# MacroPad.net
KiCad netlist of a schematic drawn in EAGLE
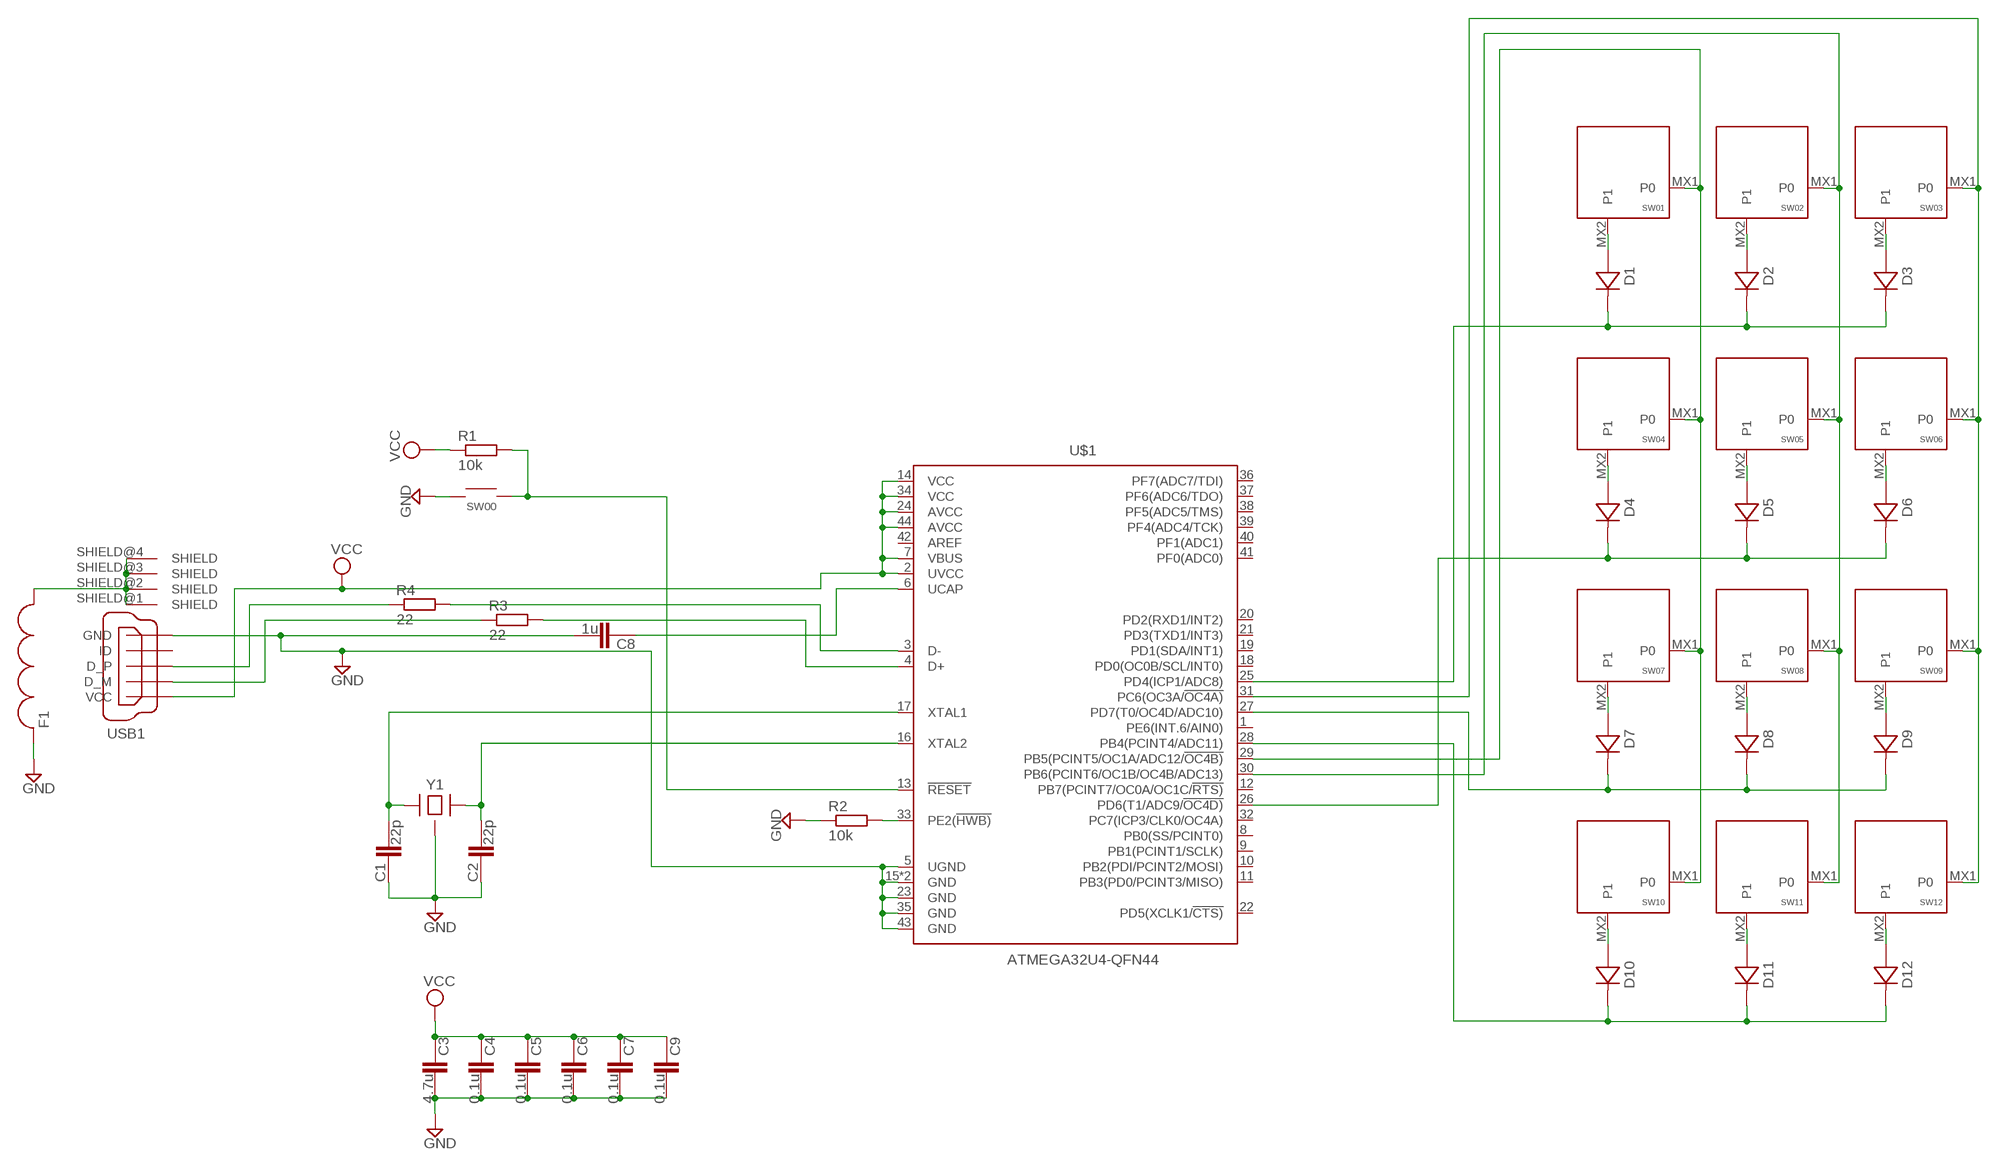
[diagram p0: schematic, sheet 1]

(export (version "E")
  (design (tool "Eeschema 10.0.6"))
  (components
    (comp (ref "C1")
      (value "22p")
      (footprint "eagle-import:C0603")
      (libsource (lib "eagle-import") (part "CAPACITOR-0603"))
    )
    (comp (ref "C2")
      (value "22p")
      (footprint "eagle-import:C0603")
      (libsource (lib "eagle-import") (part "CAPACITOR-0603"))
    )
    (comp (ref "C3")
      (value "4.7u")
      (footprint "eagle-import:C0603")
      (libsource (lib "eagle-import") (part "CAPACITOR-0603"))
    )
    (comp (ref "C4")
      (value "0.1u")
      (footprint "eagle-import:C0603")
      (libsource (lib "eagle-import") (part "CAPACITOR-0603"))
    )
    (comp (ref "C5")
      (value "0.1u")
      (footprint "eagle-import:C0603")
      (libsource (lib "eagle-import") (part "CAPACITOR-0603"))
    )
    (comp (ref "C6")
      (value "0.1u")
      (footprint "eagle-import:C0603")
      (libsource (lib "eagle-import") (part "CAPACITOR-0603"))
    )
    (comp (ref "C7")
      (value "0.1u")
      (footprint "eagle-import:C0603")
      (libsource (lib "eagle-import") (part "CAPACITOR-0603"))
    )
    (comp (ref "C8")
      (value "1u")
      (footprint "eagle-import:C0603")
      (libsource (lib "eagle-import") (part "CAPACITOR-0603"))
    )
    (comp (ref "C9")
      (value "0.1u")
      (footprint "eagle-import:C0603")
      (libsource (lib "eagle-import") (part "CAPACITOR-0603"))
    )
    (comp (ref "D1")
      (value "DIODE-DFN0603-2")
      (footprint "eagle-import:DFN0603-2")
      (libsource (lib "eagle-import") (part "DIODE-DFN0603-2"))
    )
    (comp (ref "D2")
      (value "DIODE-DFN0603-2")
      (footprint "eagle-import:DFN0603-2")
      (libsource (lib "eagle-import") (part "DIODE-DFN0603-2"))
    )
    (comp (ref "D3")
      (value "DIODE-DFN0603-2")
      (footprint "eagle-import:DFN0603-2")
      (libsource (lib "eagle-import") (part "DIODE-DFN0603-2"))
    )
    (comp (ref "D4")
      (value "DIODE-DFN0603-2")
      (footprint "eagle-import:DFN0603-2")
      (libsource (lib "eagle-import") (part "DIODE-DFN0603-2"))
    )
    (comp (ref "D5")
      (value "DIODE-DFN0603-2")
      (footprint "eagle-import:DFN0603-2")
      (libsource (lib "eagle-import") (part "DIODE-DFN0603-2"))
    )
    (comp (ref "D6")
      (value "DIODE-DFN0603-2")
      (footprint "eagle-import:DFN0603-2")
      (libsource (lib "eagle-import") (part "DIODE-DFN0603-2"))
    )
    (comp (ref "D7")
      (value "DIODE-DFN0603-2")
      (footprint "eagle-import:DFN0603-2")
      (libsource (lib "eagle-import") (part "DIODE-DFN0603-2"))
    )
    (comp (ref "D8")
      (value "DIODE-DFN0603-2")
      (footprint "eagle-import:DFN0603-2")
      (libsource (lib "eagle-import") (part "DIODE-DFN0603-2"))
    )
    (comp (ref "D9")
      (value "DIODE-DFN0603-2")
      (footprint "eagle-import:DFN0603-2")
      (libsource (lib "eagle-import") (part "DIODE-DFN0603-2"))
    )
    (comp (ref "D10")
      (value "DIODE-DFN0603-2")
      (footprint "eagle-import:DFN0603-2")
      (libsource (lib "eagle-import") (part "DIODE-DFN0603-2"))
    )
    (comp (ref "D11")
      (value "DIODE-DFN0603-2")
      (footprint "eagle-import:DFN0603-2")
      (libsource (lib "eagle-import") (part "DIODE-DFN0603-2"))
    )
    (comp (ref "D12")
      (value "DIODE-DFN0603-2")
      (footprint "eagle-import:DFN0603-2")
      (libsource (lib "eagle-import") (part "DIODE-DFN0603-2"))
    )
    (comp (ref "F1")
      (value "FERRITE-0805")
      (footprint "eagle-import:F0805")
      (libsource (lib "eagle-import") (part "FERRITE-0805"))
    )
    (comp (ref "R1")
      (value "10k")
      (footprint "eagle-import:R0603")
      (libsource (lib "eagle-import") (part "RESISTOR-0603"))
    )
    (comp (ref "R2")
      (value "10k")
      (footprint "eagle-import:R0603")
      (libsource (lib "eagle-import") (part "RESISTOR-0603"))
    )
    (comp (ref "R3")
      (value "22")
      (footprint "eagle-import:R0603")
      (libsource (lib "eagle-import") (part "RESISTOR-0603"))
    )
    (comp (ref "R4")
      (value "22")
      (footprint "eagle-import:R0603")
      (libsource (lib "eagle-import") (part "RESISTOR-0603"))
    )
    (comp (ref "SW00")
      (value "SWITCH-SMD-EVQP-P2602W")
      (footprint "eagle-import:SWITCH-SMD-EVQP-P2602W")
      (libsource (lib "eagle-import") (part "SWITCH-SMD-EVQP-P2602W"))
    )
    (comp (ref "SW01")
      (value "KEYSWITCH-PLAIN-MX-1U")
      (footprint "eagle-import:MX-1U")
      (libsource (lib "eagle-import") (part "KEYSWITCH-PLAIN-MX-1U"))
    )
    (comp (ref "SW02")
      (value "KEYSWITCH-PLAIN-MX-1U")
      (footprint "eagle-import:MX-1U")
      (libsource (lib "eagle-import") (part "KEYSWITCH-PLAIN-MX-1U"))
    )
    (comp (ref "SW03")
      (value "KEYSWITCH-PLAIN-MX-1U")
      (footprint "eagle-import:MX-1U")
      (libsource (lib "eagle-import") (part "KEYSWITCH-PLAIN-MX-1U"))
    )
    (comp (ref "SW04")
      (value "KEYSWITCH-PLAIN-MX-1U")
      (footprint "eagle-import:MX-1U")
      (libsource (lib "eagle-import") (part "KEYSWITCH-PLAIN-MX-1U"))
    )
    (comp (ref "SW05")
      (value "KEYSWITCH-PLAIN-MX-1U")
      (footprint "eagle-import:MX-1U")
      (libsource (lib "eagle-import") (part "KEYSWITCH-PLAIN-MX-1U"))
    )
    (comp (ref "SW06")
      (value "KEYSWITCH-PLAIN-MX-1U")
      (footprint "eagle-import:MX-1U")
      (libsource (lib "eagle-import") (part "KEYSWITCH-PLAIN-MX-1U"))
    )
    (comp (ref "SW07")
      (value "KEYSWITCH-PLAIN-MX-1U")
      (footprint "eagle-import:MX-1U")
      (libsource (lib "eagle-import") (part "KEYSWITCH-PLAIN-MX-1U"))
    )
    (comp (ref "SW08")
      (value "KEYSWITCH-PLAIN-MX-1U")
      (footprint "eagle-import:MX-1U")
      (libsource (lib "eagle-import") (part "KEYSWITCH-PLAIN-MX-1U"))
    )
    (comp (ref "SW09")
      (value "KEYSWITCH-PLAIN-MX-1U")
      (footprint "eagle-import:MX-1U")
      (libsource (lib "eagle-import") (part "KEYSWITCH-PLAIN-MX-1U"))
    )
    (comp (ref "SW10")
      (value "KEYSWITCH-PLAIN-MX-1U")
      (footprint "eagle-import:MX-1U")
      (libsource (lib "eagle-import") (part "KEYSWITCH-PLAIN-MX-1U"))
    )
    (comp (ref "SW11")
      (value "KEYSWITCH-PLAIN-MX-1U")
      (footprint "eagle-import:MX-1U")
      (libsource (lib "eagle-import") (part "KEYSWITCH-PLAIN-MX-1U"))
    )
    (comp (ref "SW12")
      (value "KEYSWITCH-PLAIN-MX-1U")
      (footprint "eagle-import:MX-1U")
      (libsource (lib "eagle-import") (part "KEYSWITCH-PLAIN-MX-1U"))
    )
    (comp (ref "U$1")
      (value "ATMEGA32U4-QFN44")
      (footprint "eagle-import:QFN-44")
      (libsource (lib "eagle-import") (part "ATMEGA32U4-QFN44"))
    )
    (comp (ref "USB1")
      (value "USB_CONN-MINI-FEMALE")
      (footprint "eagle-import:UX60-MB-5S8")
      (libsource (lib "eagle-import") (part "USB_CONN-MINI-FEMALE"))
    )
    (comp (ref "Y1")
      (value "CRYSTAL-4PIN-3.2X2.5")
      (footprint "eagle-import:CRYSTAL-3.2X2.5")
      (libsource (lib "eagle-import") (part "CRYSTAL-4PIN-3.2X2.5"))
    )
  )
  (nets
    (net (code "1") (name "GND") (class "Default")
      (node (ref "C1") (pin "1") (pinfunction "1_1") (pintype "passive"))
      (node (ref "C2") (pin "1") (pinfunction "1_1") (pintype "passive"))
      (node (ref "C3") (pin "2") (pinfunction "2_2") (pintype "passive"))
      (node (ref "C4") (pin "2") (pinfunction "2_2") (pintype "passive"))
      (node (ref "C5") (pin "2") (pinfunction "2_2") (pintype "passive"))
      (node (ref "C6") (pin "2") (pinfunction "2_2") (pintype "passive"))
      (node (ref "C7") (pin "2") (pinfunction "2_2") (pintype "passive"))
      (node (ref "C8") (pin "2") (pinfunction "2_2") (pintype "passive"))
      (node (ref "C9") (pin "2") (pinfunction "2_2") (pintype "passive"))
      (node (ref "F1") (pin "1") (pinfunction "P$1_1") (pintype "bidirectional"))
      (node (ref "R2") (pin "1") (pinfunction "1_1") (pintype "passive"))
      (node (ref "SW00") (pin "1A") (pinfunction "1_1A") (pintype "passive"))
      (node (ref "SW00") (pin "1B") (pinfunction "1_1B") (pintype "passive"))
      (node (ref "U$1") (pin "15") (pinfunction "GND_15") (pintype "bidirectional"))
      (node (ref "U$1") (pin "23") (pinfunction "GND_23") (pintype "bidirectional"))
      (node (ref "U$1") (pin "35") (pinfunction "GND_35") (pintype "bidirectional"))
      (node (ref "U$1") (pin "43") (pinfunction "GND_43") (pintype "bidirectional"))
      (node (ref "U$1") (pin "5") (pinfunction "UGND_5") (pintype "bidirectional"))
      (node (ref "U$1") (pin "TAB") (pinfunction "GND_TAB") (pintype "bidirectional"))
      (node (ref "USB1") (pin "GND") (pinfunction "GND_GND") (pintype "input"))
      (node (ref "Y1") (pin "2") (pinfunction "GND_2") (pintype "bidirectional"))
      (node (ref "Y1") (pin "4") (pinfunction "GND_4") (pintype "bidirectional"))
    )
    (net (code "2") (name "Net-(F1-P$2)") (class "Default")
      (node (ref "F1") (pin "2") (pinfunction "P$2_2") (pintype "bidirectional"))
      (node (ref "USB1") (pin "SHIELD@1") (pinfunction "SHIELD_SHIELD@1") (pintype "bidirectional"))
      (node (ref "USB1") (pin "SHIELD@2") (pinfunction "SHIELD_SHIELD@2") (pintype "bidirectional"))
      (node (ref "USB1") (pin "SHIELD@3") (pinfunction "SHIELD_SHIELD@3") (pintype "bidirectional"))
      (node (ref "USB1") (pin "SHIELD@4") (pinfunction "SHIELD_SHIELD@4") (pintype "bidirectional"))
    )
    (net (code "3") (name "Net-(SW01-P0)") (class "Default")
      (node (ref "SW01") (pin "MX1") (pinfunction "P0_MX1") (pintype "bidirectional"))
      (node (ref "SW04") (pin "MX1") (pinfunction "P0_MX1") (pintype "bidirectional"))
      (node (ref "SW07") (pin "MX1") (pinfunction "P0_MX1") (pintype "bidirectional"))
      (node (ref "SW10") (pin "MX1") (pinfunction "P0_MX1") (pintype "bidirectional"))
      (node (ref "U$1") (pin "29") (pinfunction "PB5(PCINT5/OC1A/ADC12/~{OC4B})_29") (pintype "bidirectional"))
    )
    (net (code "4") (name "Net-(SW01-P1)") (class "Default")
      (node (ref "D1") (pin "A") (pinfunction "A_A") (pintype "passive"))
      (node (ref "SW01") (pin "MX2") (pinfunction "P1_MX2") (pintype "bidirectional"))
    )
    (net (code "5") (name "Net-(SW02-P0)") (class "Default")
      (node (ref "SW02") (pin "MX1") (pinfunction "P0_MX1") (pintype "bidirectional"))
      (node (ref "SW05") (pin "MX1") (pinfunction "P0_MX1") (pintype "bidirectional"))
      (node (ref "SW08") (pin "MX1") (pinfunction "P0_MX1") (pintype "bidirectional"))
      (node (ref "SW11") (pin "MX1") (pinfunction "P0_MX1") (pintype "bidirectional"))
      (node (ref "U$1") (pin "30") (pinfunction "PB6(PCINT6/OC1B/OC4B/ADC13)_30") (pintype "bidirectional"))
    )
    (net (code "6") (name "Net-(SW02-P1)") (class "Default")
      (node (ref "D2") (pin "A") (pinfunction "A_A") (pintype "passive"))
      (node (ref "SW02") (pin "MX2") (pinfunction "P1_MX2") (pintype "bidirectional"))
    )
    (net (code "7") (name "Net-(SW03-P0)") (class "Default")
      (node (ref "SW03") (pin "MX1") (pinfunction "P0_MX1") (pintype "bidirectional"))
      (node (ref "SW06") (pin "MX1") (pinfunction "P0_MX1") (pintype "bidirectional"))
      (node (ref "SW09") (pin "MX1") (pinfunction "P0_MX1") (pintype "bidirectional"))
      (node (ref "SW12") (pin "MX1") (pinfunction "P0_MX1") (pintype "bidirectional"))
      (node (ref "U$1") (pin "31") (pinfunction "PC6(OC3A/~{OC4A})_31") (pintype "bidirectional"))
    )
    (net (code "8") (name "Net-(SW03-P1)") (class "Default")
      (node (ref "D3") (pin "A") (pinfunction "A_A") (pintype "passive"))
      (node (ref "SW03") (pin "MX2") (pinfunction "P1_MX2") (pintype "bidirectional"))
    )
    (net (code "9") (name "Net-(SW04-P1)") (class "Default")
      (node (ref "D4") (pin "A") (pinfunction "A_A") (pintype "passive"))
      (node (ref "SW04") (pin "MX2") (pinfunction "P1_MX2") (pintype "bidirectional"))
    )
    (net (code "10") (name "Net-(SW05-P1)") (class "Default")
      (node (ref "D5") (pin "A") (pinfunction "A_A") (pintype "passive"))
      (node (ref "SW05") (pin "MX2") (pinfunction "P1_MX2") (pintype "bidirectional"))
    )
    (net (code "11") (name "Net-(SW06-P1)") (class "Default")
      (node (ref "D6") (pin "A") (pinfunction "A_A") (pintype "passive"))
      (node (ref "SW06") (pin "MX2") (pinfunction "P1_MX2") (pintype "bidirectional"))
    )
    (net (code "12") (name "Net-(SW07-P1)") (class "Default")
      (node (ref "D7") (pin "A") (pinfunction "A_A") (pintype "passive"))
      (node (ref "SW07") (pin "MX2") (pinfunction "P1_MX2") (pintype "bidirectional"))
    )
    (net (code "13") (name "Net-(SW08-P1)") (class "Default")
      (node (ref "D8") (pin "A") (pinfunction "A_A") (pintype "passive"))
      (node (ref "SW08") (pin "MX2") (pinfunction "P1_MX2") (pintype "bidirectional"))
    )
    (net (code "14") (name "Net-(SW09-P1)") (class "Default")
      (node (ref "D9") (pin "A") (pinfunction "A_A") (pintype "passive"))
      (node (ref "SW09") (pin "MX2") (pinfunction "P1_MX2") (pintype "bidirectional"))
    )
    (net (code "15") (name "Net-(SW10-P1)") (class "Default")
      (node (ref "D10") (pin "A") (pinfunction "A_A") (pintype "passive"))
      (node (ref "SW10") (pin "MX2") (pinfunction "P1_MX2") (pintype "bidirectional"))
    )
    (net (code "16") (name "Net-(SW11-P1)") (class "Default")
      (node (ref "D11") (pin "A") (pinfunction "A_A") (pintype "passive"))
      (node (ref "SW11") (pin "MX2") (pinfunction "P1_MX2") (pintype "bidirectional"))
    )
    (net (code "17") (name "Net-(SW12-P1)") (class "Default")
      (node (ref "D12") (pin "A") (pinfunction "A_A") (pintype "passive"))
      (node (ref "SW12") (pin "MX2") (pinfunction "P1_MX2") (pintype "bidirectional"))
    )
    (net (code "18") (name "Net-(U$1-D+)") (class "Default")
      (node (ref "R3") (pin "2") (pinfunction "2_2") (pintype "passive"))
      (node (ref "U$1") (pin "4") (pinfunction "D+_4") (pintype "bidirectional"))
    )
    (net (code "19") (name "Net-(U$1-D-)") (class "Default")
      (node (ref "R4") (pin "2") (pinfunction "2_2") (pintype "passive"))
      (node (ref "U$1") (pin "3") (pinfunction "D-_3") (pintype "bidirectional"))
    )
    (net (code "20") (name "Net-(U$1-PB4(PCINT4{slash}ADC11))") (class "Default")
      (node (ref "D10") (pin "C") (pinfunction "C_C") (pintype "passive"))
      (node (ref "D11") (pin "C") (pinfunction "C_C") (pintype "passive"))
      (node (ref "D12") (pin "C") (pinfunction "C_C") (pintype "passive"))
      (node (ref "U$1") (pin "28") (pinfunction "PB4(PCINT4/ADC11)_28") (pintype "bidirectional"))
    )
    (net (code "21") (name "Net-(U$1-PD4(ICP1{slash}ADC8))") (class "Default")
      (node (ref "D1") (pin "C") (pinfunction "C_C") (pintype "passive"))
      (node (ref "D2") (pin "C") (pinfunction "C_C") (pintype "passive"))
      (node (ref "D3") (pin "C") (pinfunction "C_C") (pintype "passive"))
      (node (ref "U$1") (pin "25") (pinfunction "PD4(ICP1/ADC8)_25") (pintype "bidirectional"))
    )
    (net (code "22") (name "Net-(U$1-PD6(T1{slash}ADC9{slash}~{OC4D}))") (class "Default")
      (node (ref "D4") (pin "C") (pinfunction "C_C") (pintype "passive"))
      (node (ref "D5") (pin "C") (pinfunction "C_C") (pintype "passive"))
      (node (ref "D6") (pin "C") (pinfunction "C_C") (pintype "passive"))
      (node (ref "U$1") (pin "26") (pinfunction "PD6(T1/ADC9/~{OC4D})_26") (pintype "bidirectional"))
    )
    (net (code "23") (name "Net-(U$1-PD7(T0{slash}OC4D{slash}ADC10))") (class "Default")
      (node (ref "D7") (pin "C") (pinfunction "C_C") (pintype "passive"))
      (node (ref "D8") (pin "C") (pinfunction "C_C") (pintype "passive"))
      (node (ref "D9") (pin "C") (pinfunction "C_C") (pintype "passive"))
      (node (ref "U$1") (pin "27") (pinfunction "PD7(T0/OC4D/ADC10)_27") (pintype "bidirectional"))
    )
    (net (code "24") (name "Net-(U$1-PE2(~{HWB}))") (class "Default")
      (node (ref "R2") (pin "2") (pinfunction "2_2") (pintype "passive"))
      (node (ref "U$1") (pin "33") (pinfunction "PE2(~{HWB})_33") (pintype "bidirectional"))
    )
    (net (code "25") (name "Net-(U$1-UCAP)") (class "Default")
      (node (ref "C8") (pin "1") (pinfunction "1_1") (pintype "passive"))
      (node (ref "U$1") (pin "6") (pinfunction "UCAP_6") (pintype "bidirectional"))
    )
    (net (code "26") (name "Net-(U$1-XTAL1)") (class "Default")
      (node (ref "C1") (pin "2") (pinfunction "2_2") (pintype "passive"))
      (node (ref "U$1") (pin "17") (pinfunction "XTAL1_17") (pintype "bidirectional"))
      (node (ref "Y1") (pin "1") (pinfunction "1_1") (pintype "passive"))
    )
    (net (code "27") (name "Net-(U$1-XTAL2)") (class "Default")
      (node (ref "C2") (pin "2") (pinfunction "2_2") (pintype "passive"))
      (node (ref "U$1") (pin "16") (pinfunction "XTAL2_16") (pintype "bidirectional"))
      (node (ref "Y1") (pin "3") (pinfunction "2_3") (pintype "passive"))
    )
    (net (code "28") (name "Net-(U$1-~{RESET})") (class "Default")
      (node (ref "R1") (pin "2") (pinfunction "2_2") (pintype "passive"))
      (node (ref "SW00") (pin "2A") (pinfunction "2_2A") (pintype "passive"))
      (node (ref "SW00") (pin "2B") (pinfunction "2_2B") (pintype "passive"))
      (node (ref "U$1") (pin "13") (pinfunction "~{RESET}_13") (pintype "bidirectional"))
    )
    (net (code "29") (name "Net-(USB1-D_M)") (class "Default")
      (node (ref "R3") (pin "1") (pinfunction "1_1") (pintype "passive"))
      (node (ref "USB1") (pin "D-") (pinfunction "D_M_D-") (pintype "input"))
    )
    (net (code "30") (name "Net-(USB1-D_P)") (class "Default")
      (node (ref "R4") (pin "1") (pinfunction "1_1") (pintype "passive"))
      (node (ref "USB1") (pin "D+") (pinfunction "D_P_D+") (pintype "input"))
    )
    (net (code "31") (name "VCC") (class "Default")
      (node (ref "C3") (pin "1") (pinfunction "1_1") (pintype "passive"))
      (node (ref "C4") (pin "1") (pinfunction "1_1") (pintype "passive"))
      (node (ref "C5") (pin "1") (pinfunction "1_1") (pintype "passive"))
      (node (ref "C6") (pin "1") (pinfunction "1_1") (pintype "passive"))
      (node (ref "C7") (pin "1") (pinfunction "1_1") (pintype "passive"))
      (node (ref "C9") (pin "1") (pinfunction "1_1") (pintype "passive"))
      (node (ref "R1") (pin "1") (pinfunction "1_1") (pintype "passive"))
      (node (ref "U$1") (pin "14") (pinfunction "VCC_14") (pintype "bidirectional"))
      (node (ref "U$1") (pin "2") (pinfunction "UVCC_2") (pintype "bidirectional"))
      (node (ref "U$1") (pin "24") (pinfunction "AVCC_24") (pintype "bidirectional"))
      (node (ref "U$1") (pin "34") (pinfunction "VCC_34") (pintype "bidirectional"))
      (node (ref "U$1") (pin "44") (pinfunction "AVCC_44") (pintype "bidirectional"))
      (node (ref "U$1") (pin "7") (pinfunction "VBUS_7") (pintype "bidirectional"))
      (node (ref "USB1") (pin "VCC") (pinfunction "VCC_VCC") (pintype "input"))
    )
    (net (code "32") (name "unconnected-(U$1-AREF-Pad42)") (class "Default")
      (node (ref "U$1") (pin "42") (pinfunction "AREF_42") (pintype "bidirectional"))
    )
    (net (code "33") (name "unconnected-(U$1-PB0(SS{slash}PCINT0)-Pad8)") (class "Default")
      (node (ref "U$1") (pin "8") (pinfunction "PB0(SS/PCINT0)_8") (pintype "bidirectional"))
    )
    (net (code "34") (name "unconnected-(U$1-PB1(PCINT1{slash}SCLK)-Pad9)") (class "Default")
      (node (ref "U$1") (pin "9") (pinfunction "PB1(PCINT1/SCLK)_9") (pintype "bidirectional"))
    )
    (net (code "35") (name "unconnected-(U$1-PB2(PDI{slash}PCINT2{slash}MOSI)-Pad10)") (class "Default")
      (node (ref "U$1") (pin "10") (pinfunction "PB2(PDI/PCINT2/MOSI)_10") (pintype "bidirectional"))
    )
    (net (code "36") (name "unconnected-(U$1-PB3(PD0{slash}PCINT3{slash}MISO)-Pad11)") (class "Default")
      (node (ref "U$1") (pin "11") (pinfunction "PB3(PD0/PCINT3/MISO)_11") (pintype "bidirectional"))
    )
    (net (code "37") (name "unconnected-(U$1-PB7(PCINT7{slash}OC0A{slash}OC1C{slash}~{RTS})-Pad12)") (class "Default")
      (node (ref "U$1") (pin "12") (pinfunction "PB7(PCINT7/OC0A/OC1C/~{RTS})_12") (pintype "bidirectional"))
    )
    (net (code "38") (name "unconnected-(U$1-PC7(ICP3{slash}CLK0{slash}OC4A)-Pad32)") (class "Default")
      (node (ref "U$1") (pin "32") (pinfunction "PC7(ICP3/CLK0/OC4A)_32") (pintype "bidirectional"))
    )
    (net (code "39") (name "unconnected-(U$1-PD0(OC0B{slash}SCL{slash}INT0)-Pad18)") (class "Default")
      (node (ref "U$1") (pin "18") (pinfunction "PD0(OC0B/SCL/INT0)_18") (pintype "bidirectional"))
    )
    (net (code "40") (name "unconnected-(U$1-PD1(SDA{slash}INT1)-Pad19)") (class "Default")
      (node (ref "U$1") (pin "19") (pinfunction "PD1(SDA/INT1)_19") (pintype "bidirectional"))
    )
    (net (code "41") (name "unconnected-(U$1-PD2(RXD1{slash}INT2)-Pad20)") (class "Default")
      (node (ref "U$1") (pin "20") (pinfunction "PD2(RXD1/INT2)_20") (pintype "bidirectional"))
    )
    (net (code "42") (name "unconnected-(U$1-PD3(TXD1{slash}INT3)-Pad21)") (class "Default")
      (node (ref "U$1") (pin "21") (pinfunction "PD3(TXD1/INT3)_21") (pintype "bidirectional"))
    )
    (net (code "43") (name "unconnected-(U$1-PD5(XCLK1{slash}~{CTS})-Pad22)") (class "Default")
      (node (ref "U$1") (pin "22") (pinfunction "PD5(XCLK1/~{CTS})_22") (pintype "bidirectional"))
    )
    (net (code "44") (name "unconnected-(U$1-PE6(INT.6{slash}AIN0)-Pad1)") (class "Default")
      (node (ref "U$1") (pin "1") (pinfunction "PE6(INT.6/AIN0)_1") (pintype "bidirectional"))
    )
    (net (code "45") (name "unconnected-(U$1-PF0(ADC0)-Pad41)") (class "Default")
      (node (ref "U$1") (pin "41") (pinfunction "PF0(ADC0)_41") (pintype "bidirectional"))
    )
    (net (code "46") (name "unconnected-(U$1-PF1(ADC1)-Pad40)") (class "Default")
      (node (ref "U$1") (pin "40") (pinfunction "PF1(ADC1)_40") (pintype "bidirectional"))
    )
    (net (code "47") (name "unconnected-(U$1-PF4(ADC4{slash}TCK)-Pad39)") (class "Default")
      (node (ref "U$1") (pin "39") (pinfunction "PF4(ADC4/TCK)_39") (pintype "bidirectional"))
    )
    (net (code "48") (name "unconnected-(U$1-PF5(ADC5{slash}TMS)-Pad38)") (class "Default")
      (node (ref "U$1") (pin "38") (pinfunction "PF5(ADC5/TMS)_38") (pintype "bidirectional"))
    )
    (net (code "49") (name "unconnected-(U$1-PF6(ADC6{slash}TDO)-Pad37)") (class "Default")
      (node (ref "U$1") (pin "37") (pinfunction "PF6(ADC6/TDO)_37") (pintype "bidirectional"))
    )
    (net (code "50") (name "unconnected-(U$1-PF7(ADC7{slash}TDI)-Pad36)") (class "Default")
      (node (ref "U$1") (pin "36") (pinfunction "PF7(ADC7/TDI)_36") (pintype "bidirectional"))
    )
    (net (code "51") (name "unconnected-(USB1-PadID)") (class "Default")
      (node (ref "USB1") (pin "ID") (pinfunction "ID_ID") (pintype "input"))
    )
  )
)
